# 1-2199298-2.net
KiCad netlist of a schematic drawn in Altium Designer
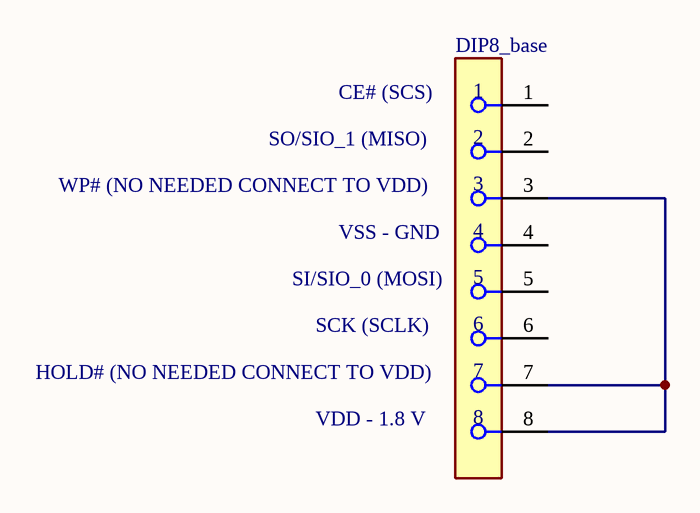
[diagram p0: 1-2199298-2.SchDoc]

(export (version "E")
  (design (tool "Eeschema 10.0.6"))
  (components
    (comp (ref "DIP8_base")
      (value "DIP8_base")
      (footprint "FP-1-2199298-2-MFG")
      (description "CONN IC DIP SOCKET 8POS TIN")
      (libsource (lib "Altium Content Vault") (part "b0a0b555dd3abf3683e7c330df25cc4"))
    )
  )
  (nets
    (net (code "1") (name "Net-(DIP8_base-Pad3)") (class "Default")
      (node (ref "DIP8_base") (pin "3") (pinfunction "3_3") (pintype "passive"))
      (node (ref "DIP8_base") (pin "7") (pinfunction "7_7") (pintype "passive"))
      (node (ref "DIP8_base") (pin "8") (pinfunction "8_8") (pintype "passive"))
    )
    (net (code "2") (name "unconnected-(DIP8_base-Pad1)") (class "Default")
      (node (ref "DIP8_base") (pin "1") (pinfunction "1_1") (pintype "passive"))
    )
    (net (code "3") (name "unconnected-(DIP8_base-Pad2)") (class "Default")
      (node (ref "DIP8_base") (pin "2") (pinfunction "2_2") (pintype "passive"))
    )
    (net (code "4") (name "unconnected-(DIP8_base-Pad4)") (class "Default")
      (node (ref "DIP8_base") (pin "4") (pinfunction "4_4") (pintype "passive"))
    )
    (net (code "5") (name "unconnected-(DIP8_base-Pad5)") (class "Default")
      (node (ref "DIP8_base") (pin "5") (pinfunction "5_5") (pintype "passive"))
    )
    (net (code "6") (name "unconnected-(DIP8_base-Pad6)") (class "Default")
      (node (ref "DIP8_base") (pin "6") (pinfunction "6_6") (pintype "passive"))
    )
  )
)
